# arduino.net
KiCad netlist of a schematic drawn in EAGLE
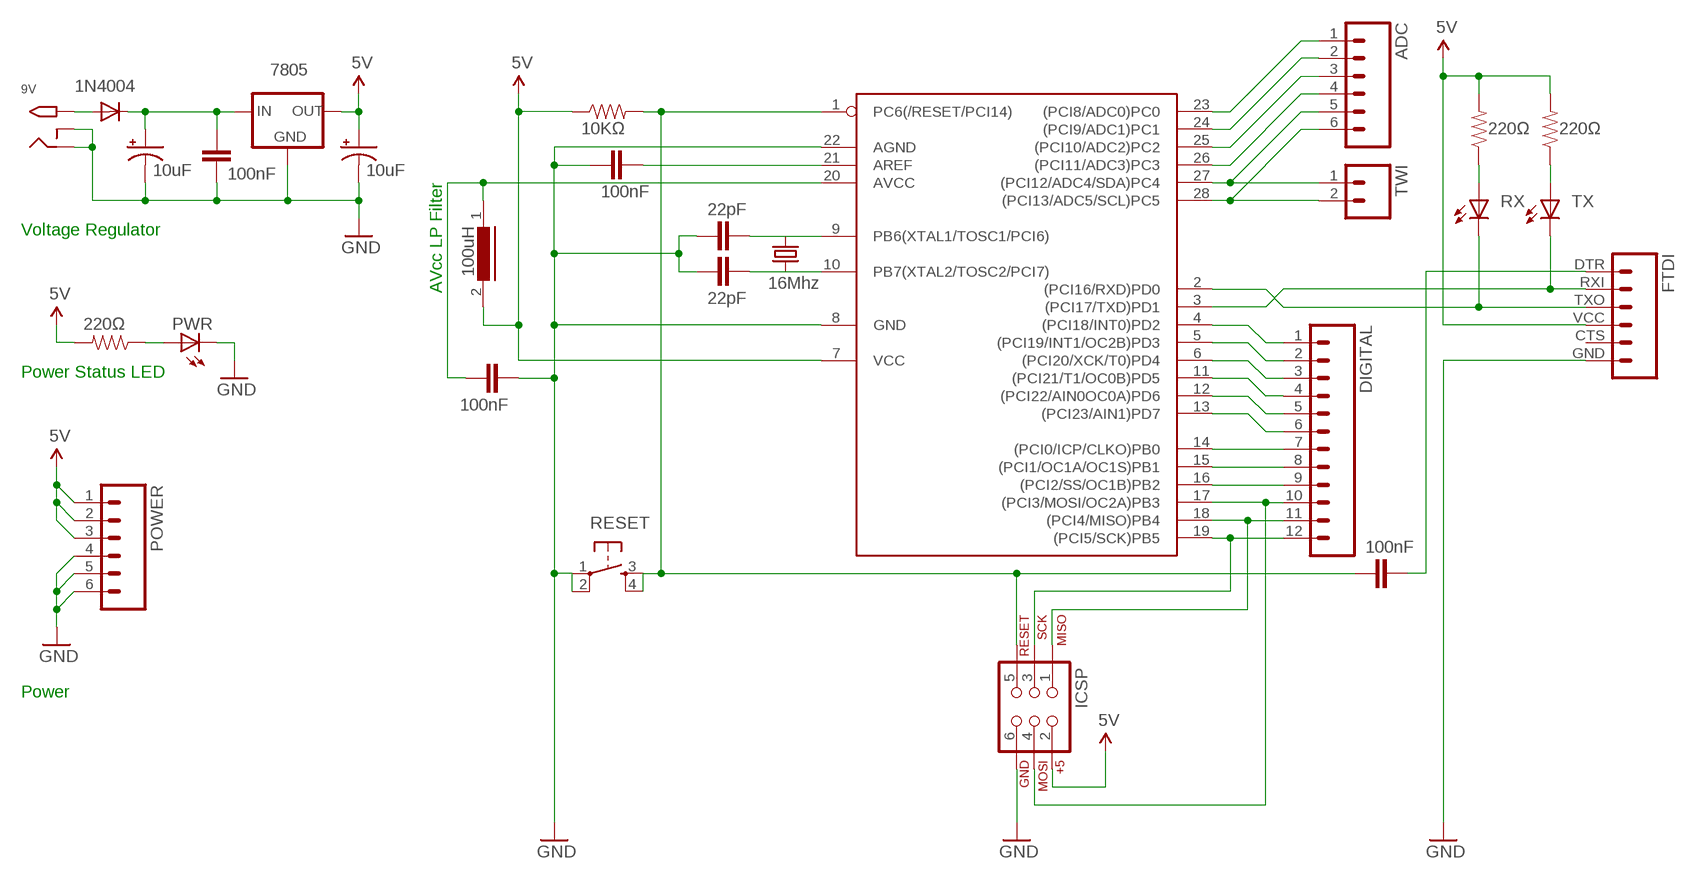
[diagram p0: schematic, sheet 1]

(export (version "E")
  (design (tool "Eeschema 10.0.6"))
  (components
    (comp (ref "9V")
      (value "2.1MMJACKTHM")
      (footprint "eagle-import:PJ-102A")
      (libsource (lib "eagle-import") (part "2.1MMJACKTHM"))
    )
    (comp (ref "ADC")
      (value "M06LOCK")
      (footprint "eagle-import:1X06_LOCK")
      (libsource (lib "eagle-import") (part "M06LOCK"))
    )
    (comp (ref "AVR_C1")
      (value "100nF")
      (footprint "eagle-import:CAP-PTH-5MM")
      (libsource (lib "eagle-import") (part "CAPPTH1"))
    )
    (comp (ref "AVR_C2")
      (value "22pF")
      (footprint "eagle-import:CAP-PTH-5MM")
      (libsource (lib "eagle-import") (part "CAPPTH1"))
    )
    (comp (ref "AVR_C3")
      (value "22pF")
      (footprint "eagle-import:CAP-PTH-5MM")
      (libsource (lib "eagle-import") (part "CAPPTH1"))
    )
    (comp (ref "AVR_C4")
      (value "100nF")
      (footprint "eagle-import:CAP-PTH-5MM")
      (libsource (lib "eagle-import") (part "CAPPTH1"))
    )
    (comp (ref "AVR_C5")
      (value "100nF")
      (footprint "eagle-import:CAP-PTH-5MM")
      (libsource (lib "eagle-import") (part "CAPPTH1"))
    )
    (comp (ref "AVR_R1")
      (value "10KΩ")
      (footprint "eagle-import:AXIAL-0.4")
      (libsource (lib "eagle-import") (part "RESISTORPTH-1/4W"))
    )
    (comp (ref "AVR_R2")
      (value "220Ω")
      (footprint "eagle-import:AXIAL-0.4")
      (libsource (lib "eagle-import") (part "RESISTORPTH-1/4W"))
    )
    (comp (ref "AVR_R3")
      (value "220Ω")
      (footprint "eagle-import:AXIAL-0.4")
      (libsource (lib "eagle-import") (part "RESISTORPTH-1/4W"))
    )
    (comp (ref "D1")
      (value "1N4004")
      (footprint "eagle-import:DO41-10")
      (libsource (lib "eagle-import") (part "1N4004"))
    )
    (comp (ref "DIGITAL")
      (value "M12LOCK")
      (footprint "eagle-import:1X12_LOCK")
      (libsource (lib "eagle-import") (part "M12LOCK"))
    )
    (comp (ref "FTDI")
      (value "FTDI_BASICPTH")
      (footprint "eagle-import:FTDI_BASIC")
      (libsource (lib "eagle-import") (part "FTDI_BASICPTH"))
    )
    (comp (ref "IC1")
      (value "ATMEGA168-20P")
      (footprint "eagle-import:DIL28-3")
      (libsource (lib "eagle-import") (part "ATMEGA168P-20"))
    )
    (comp (ref "IC2")
      (value "7805")
      (footprint "eagle-import:78XXL")
      (libsource (lib "eagle-import") (part "V_REG_78XXSIDE"))
    )
    (comp (ref "ICSP")
      (value "AVR_SPI_PRG_62X3_LOCK")
      (footprint "eagle-import:2X3_LOCK")
      (libsource (lib "eagle-import") (part "AVR_SPI_PRG_62X3_LOCK"))
    )
    (comp (ref "L1")
      (value "100uH")
      (footprint "eagle-import:MCC10")
      (libsource (lib "eagle-import") (part "MCC10"))
    )
    (comp (ref "POWER")
      (value "M06LOCK")
      (footprint "eagle-import:1X06_LOCK")
      (libsource (lib "eagle-import") (part "M06LOCK"))
    )
    (comp (ref "PWR")
      (value "LED5MM")
      (footprint "eagle-import:LED5MM")
      (libsource (lib "eagle-import") (part "LED5MM"))
    )
    (comp (ref "PWR_C1")
      (value "10uF")
      (footprint "eagle-import:CPOL-RADIAL-10UF-25V")
      (libsource (lib "eagle-import") (part "CAP_POLPTH2"))
    )
    (comp (ref "PWR_C2")
      (value "100nF")
      (footprint "eagle-import:CAP-PTH-5MM")
      (libsource (lib "eagle-import") (part "CAPPTH1"))
    )
    (comp (ref "PWR_C3")
      (value "10uF")
      (footprint "eagle-import:CPOL-RADIAL-10UF-25V")
      (libsource (lib "eagle-import") (part "CAP_POLPTH2"))
    )
    (comp (ref "PWR_R1")
      (value "220Ω")
      (footprint "eagle-import:AXIAL-0.4")
      (libsource (lib "eagle-import") (part "RESISTORPTH-1/4W"))
    )
    (comp (ref "Q1")
      (value "16Mhz")
      (footprint "eagle-import:HC49_S")
      (libsource (lib "eagle-import") (part "CRYSTALHC49S"))
    )
    (comp (ref "RESET")
      (value "TAC_SWITCHPTH")
      (footprint "eagle-import:TACTILE-PTH")
      (libsource (lib "eagle-import") (part "TAC_SWITCHPTH"))
    )
    (comp (ref "RX")
      (value "LED5MM")
      (footprint "eagle-import:LED5MM")
      (libsource (lib "eagle-import") (part "LED5MM"))
    )
    (comp (ref "TWI")
      (value "M02LOCK")
      (footprint "eagle-import:1X02_LOCK")
      (libsource (lib "eagle-import") (part "M02LOCK"))
    )
    (comp (ref "TX")
      (value "LED5MM")
      (footprint "eagle-import:LED5MM")
      (libsource (lib "eagle-import") (part "LED5MM"))
    )
  )
  (nets
    (net (code "1") (name "5V") (class "Default")
      (node (ref "AVR_R1") (pin "P$1") (pinfunction "1_P$1") (pintype "passive"))
      (node (ref "AVR_R2") (pin "P$2") (pinfunction "2_P$2") (pintype "passive"))
      (node (ref "AVR_R3") (pin "P$2") (pinfunction "2_P$2") (pintype "passive"))
      (node (ref "FTDI") (pin "VCC") (pinfunction "4_VCC") (pintype "passive"))
      (node (ref "IC1") (pin "7") (pinfunction "VCC_7") (pintype "bidirectional"))
      (node (ref "IC2") (pin "OUT") (pinfunction "OUT_OUT") (pintype "output"))
      (node (ref "ICSP") (pin "2") (pinfunction "2_2") (pintype "passive"))
      (node (ref "L1") (pin "2") (pinfunction "2_2") (pintype "passive"))
      (node (ref "POWER") (pin "1") (pinfunction "1_1") (pintype "passive"))
      (node (ref "POWER") (pin "2") (pinfunction "2_2") (pintype "passive"))
      (node (ref "POWER") (pin "3") (pinfunction "3_3") (pintype "passive"))
      (node (ref "PWR_C3") (pin "1") (pinfunction "+_1") (pintype "passive"))
      (node (ref "PWR_R1") (pin "P$2") (pinfunction "2_P$2") (pintype "passive"))
    )
    (net (code "2") (name "GND") (class "Default")
      (node (ref "9V") (pin "RING") (pinfunction "RING_RING") (pintype "bidirectional"))
      (node (ref "9V") (pin "RING_SW") (pinfunction "RING_SW_RING_SW") (pintype "bidirectional"))
      (node (ref "AVR_C1") (pin "1") (pinfunction "1_1") (pintype "passive"))
      (node (ref "AVR_C2") (pin "1") (pinfunction "1_1") (pintype "passive"))
      (node (ref "AVR_C3") (pin "1") (pinfunction "1_1") (pintype "passive"))
      (node (ref "AVR_C4") (pin "1") (pinfunction "1_1") (pintype "passive"))
      (node (ref "FTDI") (pin "GND") (pinfunction "6_GND") (pintype "passive"))
      (node (ref "IC1") (pin "22") (pinfunction "AGND_22") (pintype "bidirectional"))
      (node (ref "IC1") (pin "8") (pinfunction "GND_8") (pintype "bidirectional"))
      (node (ref "IC2") (pin "GND") (pinfunction "GND_GND") (pintype "input"))
      (node (ref "ICSP") (pin "6") (pinfunction "6_6") (pintype "passive"))
      (node (ref "POWER") (pin "4") (pinfunction "4_4") (pintype "passive"))
      (node (ref "POWER") (pin "5") (pinfunction "5_5") (pintype "passive"))
      (node (ref "POWER") (pin "6") (pinfunction "6_6") (pintype "passive"))
      (node (ref "PWR") (pin "K") (pinfunction "C_K") (pintype "passive"))
      (node (ref "PWR_C1") (pin "2") (pinfunction "-_2") (pintype "passive"))
      (node (ref "PWR_C2") (pin "1") (pinfunction "1_1") (pintype "passive"))
      (node (ref "PWR_C3") (pin "2") (pinfunction "-_2") (pintype "passive"))
      (node (ref "RESET") (pin "1") (pinfunction "1_1") (pintype "passive"))
      (node (ref "RESET") (pin "2") (pinfunction "2_2") (pintype "passive"))
    )
    (net (code "3") (name "Net-(9V-PadTIP)") (class "Default")
      (node (ref "9V") (pin "TIP") (pinfunction "TIP_TIP") (pintype "bidirectional"))
      (node (ref "D1") (pin "A") (pinfunction "A_A") (pintype "passive"))
    )
    (net (code "4") (name "Net-(AVR_R1-2)") (class "Default")
      (node (ref "AVR_C5") (pin "1") (pinfunction "1_1") (pintype "passive"))
      (node (ref "AVR_R1") (pin "P$2") (pinfunction "2_P$2") (pintype "passive"))
      (node (ref "IC1") (pin "1") (pinfunction "PC6(/RESET/PCI14)_1") (pintype "bidirectional"))
      (node (ref "ICSP") (pin "5") (pinfunction "5_5") (pintype "passive"))
      (node (ref "RESET") (pin "3") (pinfunction "3_3") (pintype "passive"))
      (node (ref "RESET") (pin "4") (pinfunction "4_4") (pintype "passive"))
    )
    (net (code "5") (name "Net-(AVR_R2-1)") (class "Default")
      (node (ref "AVR_R2") (pin "P$1") (pinfunction "1_P$1") (pintype "passive"))
      (node (ref "RX") (pin "A") (pinfunction "A_A") (pintype "passive"))
    )
    (net (code "6") (name "Net-(AVR_R3-1)") (class "Default")
      (node (ref "AVR_R3") (pin "P$1") (pinfunction "1_P$1") (pintype "passive"))
      (node (ref "TX") (pin "A") (pinfunction "A_A") (pintype "passive"))
    )
    (net (code "7") (name "Net-(FTDI-1)") (class "Default")
      (node (ref "AVR_C5") (pin "2") (pinfunction "2_2") (pintype "passive"))
      (node (ref "FTDI") (pin "DTR") (pinfunction "1_DTR") (pintype "passive"))
    )
    (net (code "8") (name "Net-(FTDI-2)") (class "Default")
      (node (ref "FTDI") (pin "RXI") (pinfunction "2_RXI") (pintype "passive"))
      (node (ref "IC1") (pin "3") (pinfunction "(PCI17/TXD)PD1_3") (pintype "bidirectional"))
      (node (ref "TX") (pin "K") (pinfunction "C_K") (pintype "passive"))
    )
    (net (code "9") (name "Net-(FTDI-3)") (class "Default")
      (node (ref "FTDI") (pin "TXO") (pinfunction "3_TXO") (pintype "passive"))
      (node (ref "IC1") (pin "2") (pinfunction "(PCI16/RXD)PD0_2") (pintype "bidirectional"))
      (node (ref "RX") (pin "K") (pinfunction "C_K") (pintype "passive"))
    )
    (net (code "10") (name "Net-(IC1-(PCI0{slash}ICP{slash}CLKO)PB0)") (class "Default")
      (node (ref "DIGITAL") (pin "7") (pinfunction "7_7") (pintype "passive"))
      (node (ref "IC1") (pin "14") (pinfunction "(PCI0/ICP/CLKO)PB0_14") (pintype "bidirectional"))
    )
    (net (code "11") (name "Net-(IC1-(PCI1{slash}OC1A{slash}OC1S)PB1)") (class "Default")
      (node (ref "DIGITAL") (pin "8") (pinfunction "8_8") (pintype "passive"))
      (node (ref "IC1") (pin "15") (pinfunction "(PCI1/OC1A/OC1S)PB1_15") (pintype "bidirectional"))
    )
    (net (code "12") (name "Net-(IC1-(PCI2{slash}SS{slash}OC1B)PB2)") (class "Default")
      (node (ref "DIGITAL") (pin "9") (pinfunction "9_9") (pintype "passive"))
      (node (ref "IC1") (pin "16") (pinfunction "(PCI2/SS/OC1B)PB2_16") (pintype "bidirectional"))
    )
    (net (code "13") (name "Net-(IC1-(PCI3{slash}MOSI{slash}OC2A)PB3)") (class "Default")
      (node (ref "DIGITAL") (pin "10") (pinfunction "10_10") (pintype "passive"))
      (node (ref "IC1") (pin "17") (pinfunction "(PCI3/MOSI/OC2A)PB3_17") (pintype "bidirectional"))
      (node (ref "ICSP") (pin "4") (pinfunction "4_4") (pintype "passive"))
    )
    (net (code "14") (name "Net-(IC1-(PCI4{slash}MISO)PB4)") (class "Default")
      (node (ref "DIGITAL") (pin "11") (pinfunction "11_11") (pintype "passive"))
      (node (ref "IC1") (pin "18") (pinfunction "(PCI4/MISO)PB4_18") (pintype "bidirectional"))
      (node (ref "ICSP") (pin "1") (pinfunction "1_1") (pintype "passive"))
    )
    (net (code "15") (name "Net-(IC1-(PCI5{slash}SCK)PB5)") (class "Default")
      (node (ref "DIGITAL") (pin "12") (pinfunction "12_12") (pintype "passive"))
      (node (ref "IC1") (pin "19") (pinfunction "(PCI5/SCK)PB5_19") (pintype "bidirectional"))
      (node (ref "ICSP") (pin "3") (pinfunction "3_3") (pintype "passive"))
    )
    (net (code "16") (name "Net-(IC1-(PCI8{slash}ADC0)PC0)") (class "Default")
      (node (ref "ADC") (pin "1") (pinfunction "1_1") (pintype "passive"))
      (node (ref "IC1") (pin "23") (pinfunction "(PCI8/ADC0)PC0_23") (pintype "bidirectional"))
    )
    (net (code "17") (name "Net-(IC1-(PCI9{slash}ADC1)PC1)") (class "Default")
      (node (ref "ADC") (pin "2") (pinfunction "2_2") (pintype "passive"))
      (node (ref "IC1") (pin "24") (pinfunction "(PCI9/ADC1)PC1_24") (pintype "bidirectional"))
    )
    (net (code "18") (name "Net-(IC1-(PCI10{slash}ADC2)PC2)") (class "Default")
      (node (ref "ADC") (pin "3") (pinfunction "3_3") (pintype "passive"))
      (node (ref "IC1") (pin "25") (pinfunction "(PCI10/ADC2)PC2_25") (pintype "bidirectional"))
    )
    (net (code "19") (name "Net-(IC1-(PCI11{slash}ADC3)PC3)") (class "Default")
      (node (ref "ADC") (pin "4") (pinfunction "4_4") (pintype "passive"))
      (node (ref "IC1") (pin "26") (pinfunction "(PCI11/ADC3)PC3_26") (pintype "bidirectional"))
    )
    (net (code "20") (name "Net-(IC1-(PCI12{slash}ADC4{slash}SDA)PC4)") (class "Default")
      (node (ref "ADC") (pin "5") (pinfunction "5_5") (pintype "passive"))
      (node (ref "IC1") (pin "27") (pinfunction "(PCI12/ADC4/SDA)PC4_27") (pintype "bidirectional"))
      (node (ref "TWI") (pin "1") (pinfunction "1_1") (pintype "passive"))
    )
    (net (code "21") (name "Net-(IC1-(PCI13{slash}ADC5{slash}SCL)PC5)") (class "Default")
      (node (ref "ADC") (pin "6") (pinfunction "6_6") (pintype "passive"))
      (node (ref "IC1") (pin "28") (pinfunction "(PCI13/ADC5/SCL)PC5_28") (pintype "bidirectional"))
      (node (ref "TWI") (pin "2") (pinfunction "2_2") (pintype "passive"))
    )
    (net (code "22") (name "Net-(IC1-(PCI18{slash}INT0)PD2)") (class "Default")
      (node (ref "DIGITAL") (pin "1") (pinfunction "1_1") (pintype "passive"))
      (node (ref "IC1") (pin "4") (pinfunction "(PCI18/INT0)PD2_4") (pintype "bidirectional"))
    )
    (net (code "23") (name "Net-(IC1-(PCI19{slash}INT1{slash}OC2B)PD3)") (class "Default")
      (node (ref "DIGITAL") (pin "2") (pinfunction "2_2") (pintype "passive"))
      (node (ref "IC1") (pin "5") (pinfunction "(PCI19/INT1/OC2B)PD3_5") (pintype "bidirectional"))
    )
    (net (code "24") (name "Net-(IC1-(PCI20{slash}XCK{slash}T0)PD4)") (class "Default")
      (node (ref "DIGITAL") (pin "3") (pinfunction "3_3") (pintype "passive"))
      (node (ref "IC1") (pin "6") (pinfunction "(PCI20/XCK/T0)PD4_6") (pintype "bidirectional"))
    )
    (net (code "25") (name "Net-(IC1-(PCI21{slash}T1{slash}OC0B)PD5)") (class "Default")
      (node (ref "DIGITAL") (pin "4") (pinfunction "4_4") (pintype "passive"))
      (node (ref "IC1") (pin "11") (pinfunction "(PCI21/T1/OC0B)PD5_11") (pintype "bidirectional"))
    )
    (net (code "26") (name "Net-(IC1-(PCI22{slash}AIN0OC0A)PD6)") (class "Default")
      (node (ref "DIGITAL") (pin "5") (pinfunction "5_5") (pintype "passive"))
      (node (ref "IC1") (pin "12") (pinfunction "(PCI22/AIN0OC0A)PD6_12") (pintype "bidirectional"))
    )
    (net (code "27") (name "Net-(IC1-(PCI23{slash}AIN1)PD7)") (class "Default")
      (node (ref "DIGITAL") (pin "6") (pinfunction "6_6") (pintype "passive"))
      (node (ref "IC1") (pin "13") (pinfunction "(PCI23/AIN1)PD7_13") (pintype "bidirectional"))
    )
    (net (code "28") (name "Net-(IC1-AREF)") (class "Default")
      (node (ref "AVR_C1") (pin "2") (pinfunction "2_2") (pintype "passive"))
      (node (ref "IC1") (pin "21") (pinfunction "AREF_21") (pintype "bidirectional"))
    )
    (net (code "29") (name "Net-(IC1-AVCC)") (class "Default")
      (node (ref "AVR_C4") (pin "2") (pinfunction "2_2") (pintype "passive"))
      (node (ref "IC1") (pin "20") (pinfunction "AVCC_20") (pintype "bidirectional"))
      (node (ref "L1") (pin "1") (pinfunction "1_1") (pintype "passive"))
    )
    (net (code "30") (name "Net-(IC1-PB6(XTAL1{slash}TOSC1{slash}PCI6))") (class "Default")
      (node (ref "AVR_C2") (pin "2") (pinfunction "2_2") (pintype "passive"))
      (node (ref "IC1") (pin "9") (pinfunction "PB6(XTAL1/TOSC1/PCI6)_9") (pintype "bidirectional"))
      (node (ref "Q1") (pin "2") (pinfunction "2_2") (pintype "passive"))
    )
    (net (code "31") (name "Net-(IC1-PB7(XTAL2{slash}TOSC2{slash}PCI7))") (class "Default")
      (node (ref "AVR_C3") (pin "2") (pinfunction "2_2") (pintype "passive"))
      (node (ref "IC1") (pin "10") (pinfunction "PB7(XTAL2/TOSC2/PCI7)_10") (pintype "bidirectional"))
      (node (ref "Q1") (pin "1") (pinfunction "1_1") (pintype "passive"))
    )
    (net (code "32") (name "Net-(PWR_C1-+)") (class "Default")
      (node (ref "D1") (pin "C") (pinfunction "C_C") (pintype "passive"))
      (node (ref "IC2") (pin "IN") (pinfunction "IN_IN") (pintype "input"))
      (node (ref "PWR_C1") (pin "1") (pinfunction "+_1") (pintype "passive"))
      (node (ref "PWR_C2") (pin "2") (pinfunction "2_2") (pintype "passive"))
    )
    (net (code "33") (name "Net-(PWR_R1-1)") (class "Default")
      (node (ref "PWR") (pin "A") (pinfunction "A_A") (pintype "passive"))
      (node (ref "PWR_R1") (pin "P$1") (pinfunction "1_P$1") (pintype "passive"))
    )
    (net (code "34") (name "unconnected-(FTDI-5-PadCTS)") (class "Default")
      (node (ref "FTDI") (pin "CTS") (pinfunction "5_CTS") (pintype "passive"))
    )
  )
)
